# pca20054_sheet3_antenna_switches.net
KiCad netlist of a schematic drawn in Altium Designer
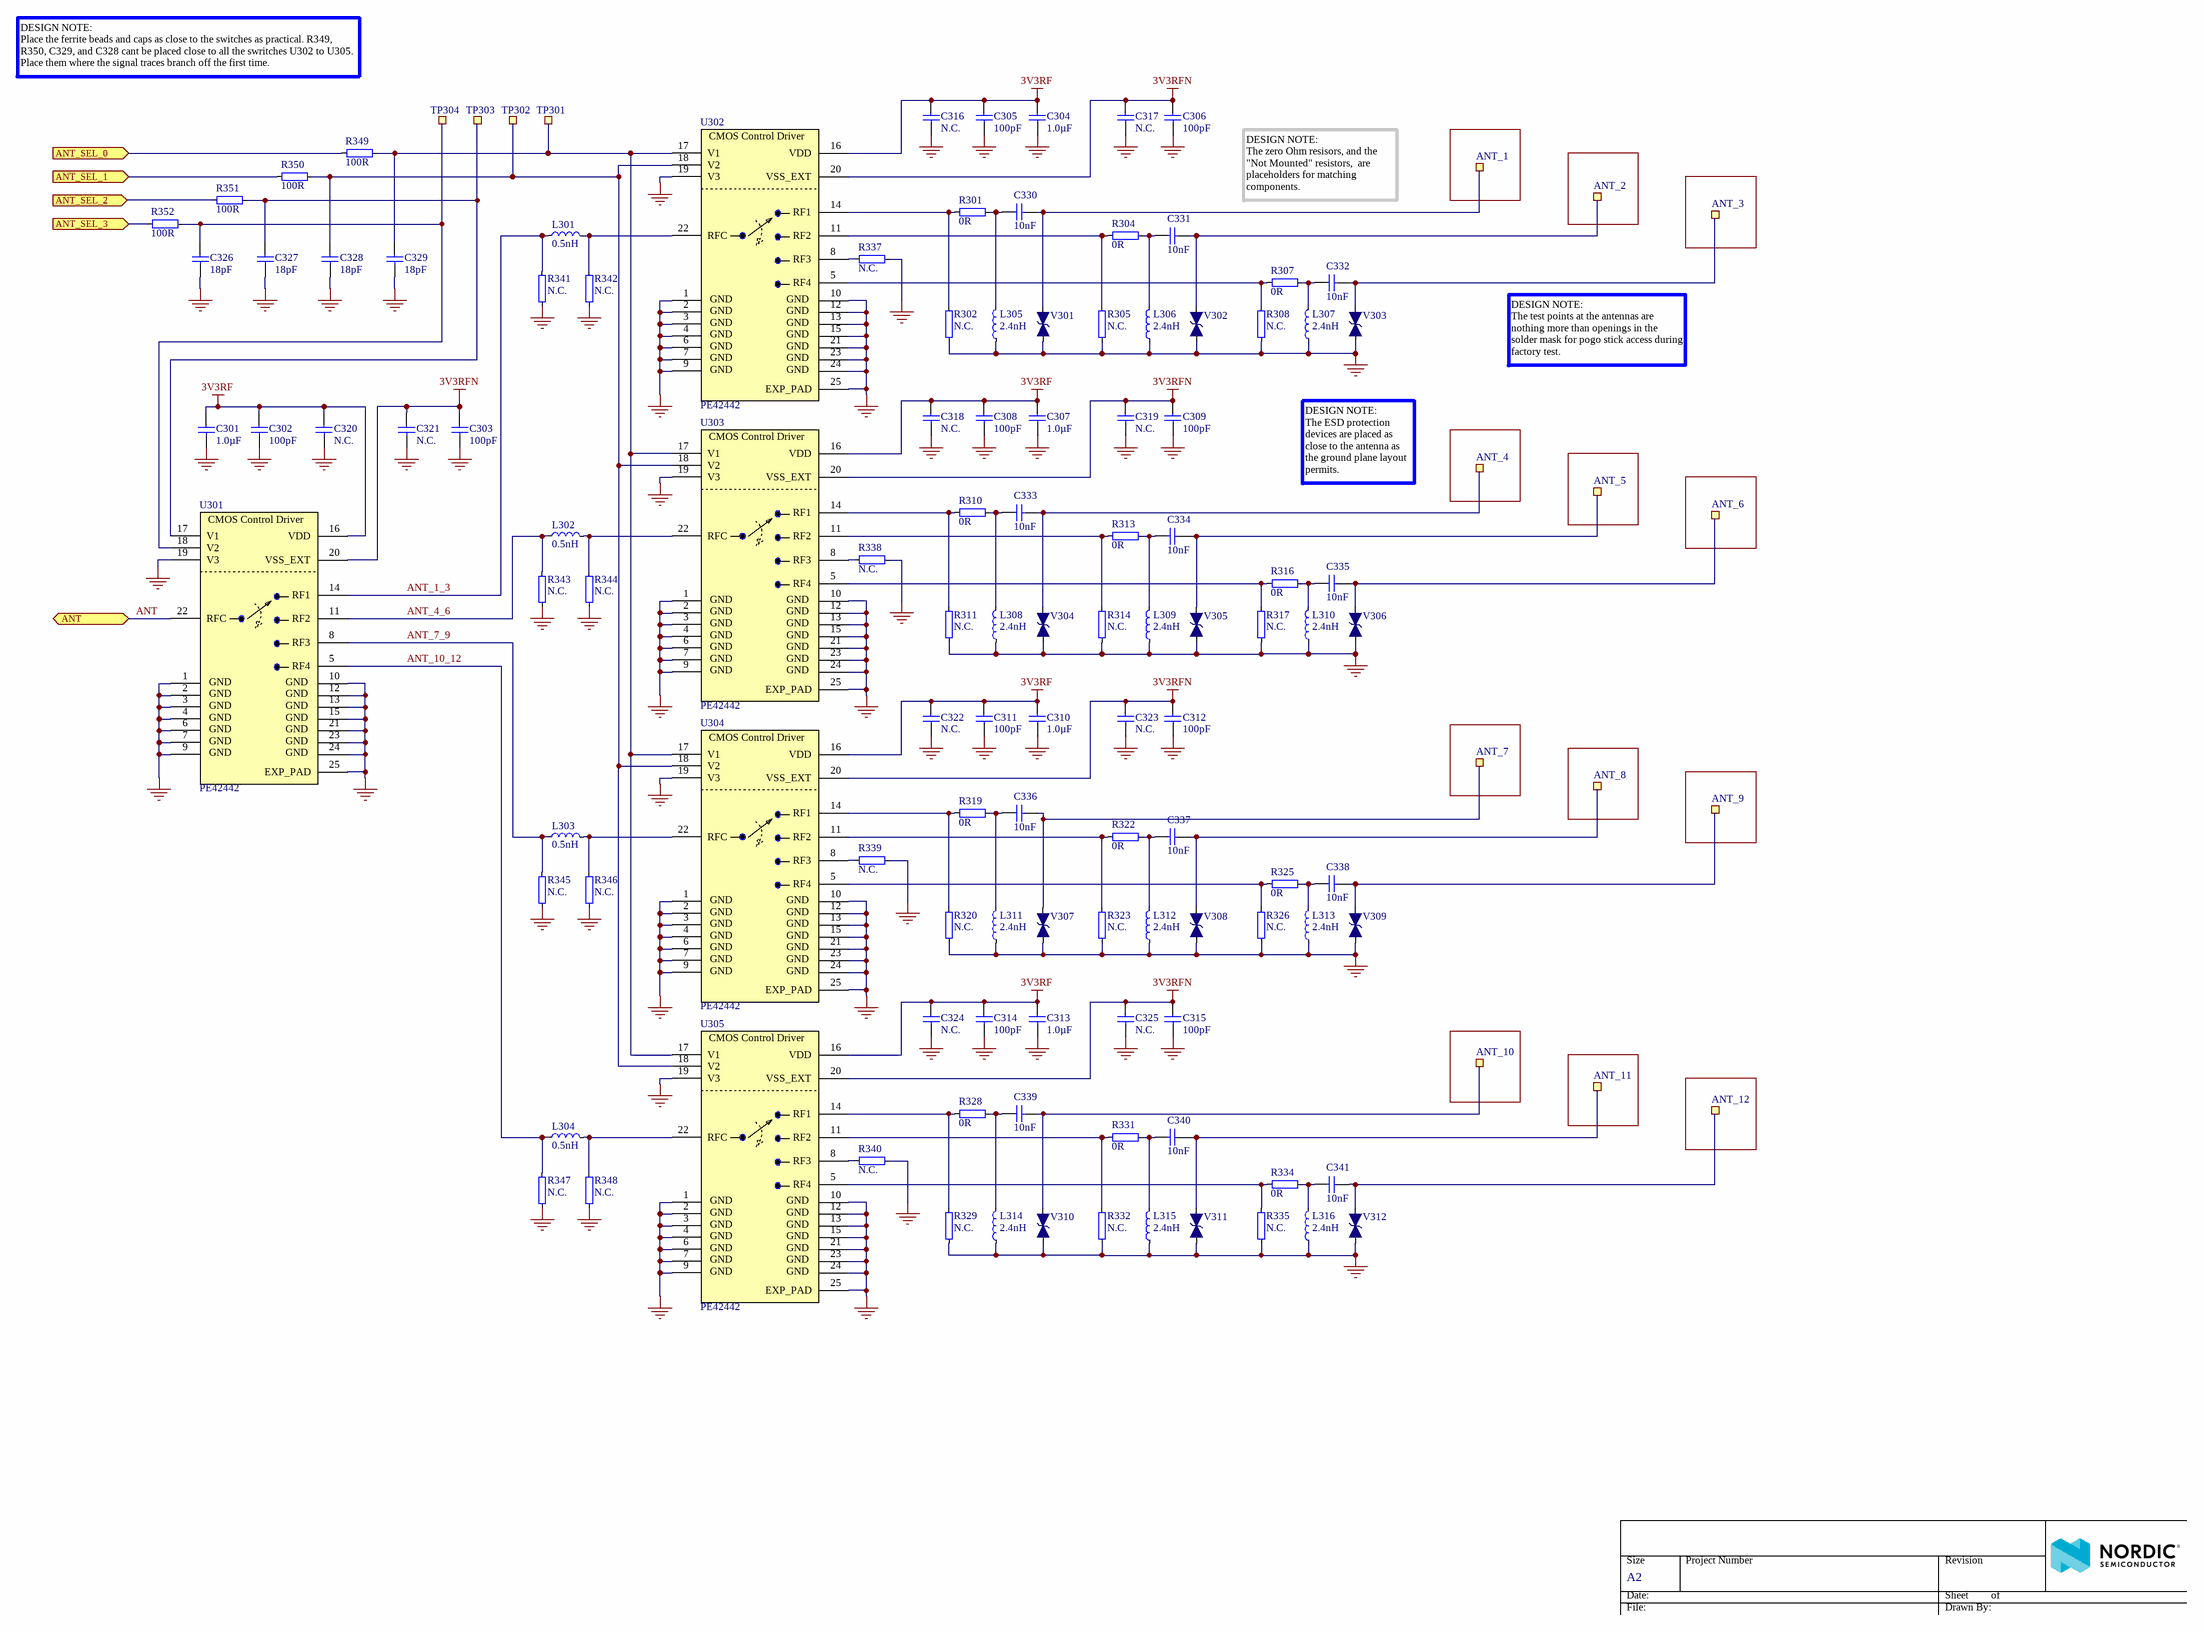
[diagram p0: pca20054_sheet3_antenna_switches.SchDoc]

(export (version "E")
  (design (tool "Eeschema 10.0.6"))
  (components
    (comp (ref "ANT_1")
      (value "Ø1.0mm,SMD")
      (footprint "TP_SMD_?.0mm")
      (description "1.0mm circular SMD testpad")
      (fields
        (field (name "PART NUMBER") "TP_SMD_Ø1.0MM")
        (field (name "MANUFACTURER") "Nordic Semiconductor")
        (field (name "PUBLISHER") "Nordic Semiconductor")
      )
      (libsource (lib "Nordic Passive DB") (part "TESTPAD"))
    )
    (comp (ref "ANT_2")
      (value "Ø1.0mm,SMD")
      (footprint "TP_SMD_?.0mm")
      (description "1.0mm circular SMD testpad")
      (fields
        (field (name "PART NUMBER") "TP_SMD_Ø1.0MM")
        (field (name "MANUFACTURER") "Nordic Semiconductor")
        (field (name "PUBLISHER") "Nordic Semiconductor")
      )
      (libsource (lib "Nordic Passive DB") (part "TESTPAD"))
    )
    (comp (ref "ANT_3")
      (value "Ø1.0mm,SMD")
      (footprint "TP_SMD_?.0mm")
      (description "1.0mm circular SMD testpad")
      (fields
        (field (name "PART NUMBER") "TP_SMD_Ø1.0MM")
        (field (name "MANUFACTURER") "Nordic Semiconductor")
        (field (name "PUBLISHER") "Nordic Semiconductor")
      )
      (libsource (lib "Nordic Passive DB") (part "TESTPAD"))
    )
    (comp (ref "ANT_4")
      (value "Ø1.0mm,SMD")
      (footprint "TP_SMD_?.0mm")
      (description "1.0mm circular SMD testpad")
      (fields
        (field (name "PART NUMBER") "TP_SMD_Ø1.0MM")
        (field (name "MANUFACTURER") "Nordic Semiconductor")
        (field (name "PUBLISHER") "Nordic Semiconductor")
      )
      (libsource (lib "Nordic Passive DB") (part "TESTPAD"))
    )
    (comp (ref "ANT_5")
      (value "Ø1.0mm,SMD")
      (footprint "TP_SMD_?.0mm")
      (description "1.0mm circular SMD testpad")
      (fields
        (field (name "PART NUMBER") "TP_SMD_Ø1.0MM")
        (field (name "MANUFACTURER") "Nordic Semiconductor")
        (field (name "PUBLISHER") "Nordic Semiconductor")
      )
      (libsource (lib "Nordic Passive DB") (part "TESTPAD"))
    )
    (comp (ref "ANT_6")
      (value "Ø1.0mm,SMD")
      (footprint "TP_SMD_?.0mm")
      (description "1.0mm circular SMD testpad")
      (fields
        (field (name "PART NUMBER") "TP_SMD_Ø1.0MM")
        (field (name "MANUFACTURER") "Nordic Semiconductor")
        (field (name "PUBLISHER") "Nordic Semiconductor")
      )
      (libsource (lib "Nordic Passive DB") (part "TESTPAD"))
    )
    (comp (ref "ANT_7")
      (value "Ø1.0mm,SMD")
      (footprint "TP_SMD_?.0mm")
      (description "1.0mm circular SMD testpad")
      (fields
        (field (name "PART NUMBER") "TP_SMD_Ø1.0MM")
        (field (name "MANUFACTURER") "Nordic Semiconductor")
        (field (name "PUBLISHER") "Nordic Semiconductor")
      )
      (libsource (lib "Nordic Passive DB") (part "TESTPAD"))
    )
    (comp (ref "ANT_8")
      (value "Ø1.0mm,SMD")
      (footprint "TP_SMD_?.0mm")
      (description "1.0mm circular SMD testpad")
      (fields
        (field (name "PART NUMBER") "TP_SMD_Ø1.0MM")
        (field (name "MANUFACTURER") "Nordic Semiconductor")
        (field (name "PUBLISHER") "Nordic Semiconductor")
      )
      (libsource (lib "Nordic Passive DB") (part "TESTPAD"))
    )
    (comp (ref "ANT_9")
      (value "Ø1.0mm,SMD")
      (footprint "TP_SMD_?.0mm")
      (description "1.0mm circular SMD testpad")
      (fields
        (field (name "PART NUMBER") "TP_SMD_Ø1.0MM")
        (field (name "MANUFACTURER") "Nordic Semiconductor")
        (field (name "PUBLISHER") "Nordic Semiconductor")
      )
      (libsource (lib "Nordic Passive DB") (part "TESTPAD"))
    )
    (comp (ref "ANT_10")
      (value "Ø1.0mm,SMD")
      (footprint "TP_SMD_?.0mm")
      (description "1.0mm circular SMD testpad")
      (fields
        (field (name "PART NUMBER") "TP_SMD_Ø1.0MM")
        (field (name "MANUFACTURER") "Nordic Semiconductor")
        (field (name "PUBLISHER") "Nordic Semiconductor")
      )
      (libsource (lib "Nordic Passive DB") (part "TESTPAD"))
    )
    (comp (ref "ANT_11")
      (value "Ø1.0mm,SMD")
      (footprint "TP_SMD_?.0mm")
      (description "1.0mm circular SMD testpad")
      (fields
        (field (name "PART NUMBER") "TP_SMD_Ø1.0MM")
        (field (name "MANUFACTURER") "Nordic Semiconductor")
        (field (name "PUBLISHER") "Nordic Semiconductor")
      )
      (libsource (lib "Nordic Passive DB") (part "TESTPAD"))
    )
    (comp (ref "ANT_12")
      (value "Ø1.0mm,SMD")
      (footprint "TP_SMD_?.0mm")
      (description "1.0mm circular SMD testpad")
      (fields
        (field (name "PART NUMBER") "TP_SMD_Ø1.0MM")
        (field (name "MANUFACTURER") "Nordic Semiconductor")
        (field (name "PUBLISHER") "Nordic Semiconductor")
      )
      (libsource (lib "Nordic Passive DB") (part "TESTPAD"))
    )
    (comp (ref "C301")
      (value "1.0µF")
      (footprint "CAPC1608X06L")
      (description "Capacitor, X7R, ±10%")
      (fields (field (name "PART NUMBER") "C0603-1µ0") (field (name "PUBLISHER") "Nordic Semiconductor"))
      (libsource (lib "Nordic Passive DB") (part "CAP"))
    )
    (comp (ref "C302")
      (value "100pF")
      (footprint "CAPC1005X04L")
      (description "Capacitor, NP0, ±5%")
      (fields (field (name "PART NUMBER") "C0402-100p") (field (name "PUBLISHER") "Nordic Semiconductor"))
      (libsource (lib "Nordic Passive DB") (part "CAP"))
    )
    (comp (ref "C303")
      (value "100pF")
      (footprint "CAPC1005X04L")
      (description "Capacitor, NP0, ±5%")
      (fields (field (name "PART NUMBER") "C0402-100p") (field (name "PUBLISHER") "Nordic Semiconductor"))
      (libsource (lib "Nordic Passive DB") (part "CAP"))
    )
    (comp (ref "C304")
      (value "1.0µF")
      (footprint "CAPC1608X06L")
      (description "Capacitor, X7R, ±10%")
      (fields (field (name "PART NUMBER") "C0603-1µ0") (field (name "PUBLISHER") "Nordic Semiconductor"))
      (libsource (lib "Nordic Passive DB") (part "CAP"))
    )
    (comp (ref "C305")
      (value "100pF")
      (footprint "CAPC1005X04L")
      (description "Capacitor, NP0, ±5%")
      (fields (field (name "PART NUMBER") "C0402-100p") (field (name "PUBLISHER") "Nordic Semiconductor"))
      (libsource (lib "Nordic Passive DB") (part "CAP"))
    )
    (comp (ref "C306")
      (value "100pF")
      (footprint "CAPC1005X04L")
      (description "Capacitor, NP0, ±5%")
      (fields (field (name "PART NUMBER") "C0402-100p") (field (name "PUBLISHER") "Nordic Semiconductor"))
      (libsource (lib "Nordic Passive DB") (part "CAP"))
    )
    (comp (ref "C307")
      (value "1.0µF")
      (footprint "CAPC1608X06L")
      (description "Capacitor, X7R, ±10%")
      (fields (field (name "PART NUMBER") "C0603-1µ0") (field (name "PUBLISHER") "Nordic Semiconductor"))
      (libsource (lib "Nordic Passive DB") (part "CAP"))
    )
    (comp (ref "C308")
      (value "100pF")
      (footprint "CAPC1005X04L")
      (description "Capacitor, NP0, ±5%")
      (fields (field (name "PART NUMBER") "C0402-100p") (field (name "PUBLISHER") "Nordic Semiconductor"))
      (libsource (lib "Nordic Passive DB") (part "CAP"))
    )
    (comp (ref "C309")
      (value "100pF")
      (footprint "CAPC1005X04L")
      (description "Capacitor, NP0, ±5%")
      (fields (field (name "PART NUMBER") "C0402-100p") (field (name "PUBLISHER") "Nordic Semiconductor"))
      (libsource (lib "Nordic Passive DB") (part "CAP"))
    )
    (comp (ref "C310")
      (value "1.0µF")
      (footprint "CAPC1608X06L")
      (description "Capacitor, X7R, ±10%")
      (fields (field (name "PART NUMBER") "C0603-1µ0") (field (name "PUBLISHER") "Nordic Semiconductor"))
      (libsource (lib "Nordic Passive DB") (part "CAP"))
    )
    (comp (ref "C311")
      (value "100pF")
      (footprint "CAPC1005X04L")
      (description "Capacitor, NP0, ±5%")
      (fields (field (name "PART NUMBER") "C0402-100p") (field (name "PUBLISHER") "Nordic Semiconductor"))
      (libsource (lib "Nordic Passive DB") (part "CAP"))
    )
    (comp (ref "C312")
      (value "100pF")
      (footprint "CAPC1005X04L")
      (description "Capacitor, NP0, ±5%")
      (fields (field (name "PART NUMBER") "C0402-100p") (field (name "PUBLISHER") "Nordic Semiconductor"))
      (libsource (lib "Nordic Passive DB") (part "CAP"))
    )
    (comp (ref "C313")
      (value "1.0µF")
      (footprint "CAPC1608X06L")
      (description "Capacitor, X7R, ±10%")
      (fields (field (name "PART NUMBER") "C0603-1µ0") (field (name "PUBLISHER") "Nordic Semiconductor"))
      (libsource (lib "Nordic Passive DB") (part "CAP"))
    )
    (comp (ref "C314")
      (value "100pF")
      (footprint "CAPC1005X04L")
      (description "Capacitor, NP0, ±5%")
      (fields (field (name "PART NUMBER") "C0402-100p") (field (name "PUBLISHER") "Nordic Semiconductor"))
      (libsource (lib "Nordic Passive DB") (part "CAP"))
    )
    (comp (ref "C315")
      (value "100pF")
      (footprint "CAPC1005X04L")
      (description "Capacitor, NP0, ±5%")
      (fields (field (name "PART NUMBER") "C0402-100p") (field (name "PUBLISHER") "Nordic Semiconductor"))
      (libsource (lib "Nordic Passive DB") (part "CAP"))
    )
    (comp (ref "C316")
      (value "N.C.")
      (footprint "CAPC1005X04L_NC")
      (description "Not mounted")
      (fields (field (name "PART NUMBER") "C0402-N.C.") (field (name "PUBLISHER") "Nordic Semiconductor"))
      (libsource (lib "Nordic Passive DB") (part "CAP"))
    )
    (comp (ref "C317")
      (value "N.C.")
      (footprint "CAPC1005X04L_NC")
      (description "Not mounted")
      (fields (field (name "PART NUMBER") "C0402-N.C.") (field (name "PUBLISHER") "Nordic Semiconductor"))
      (libsource (lib "Nordic Passive DB") (part "CAP"))
    )
    (comp (ref "C318")
      (value "N.C.")
      (footprint "CAPC1005X04L_NC")
      (description "Not mounted")
      (fields (field (name "PART NUMBER") "C0402-N.C.") (field (name "PUBLISHER") "Nordic Semiconductor"))
      (libsource (lib "Nordic Passive DB") (part "CAP"))
    )
    (comp (ref "C319")
      (value "N.C.")
      (footprint "CAPC1005X04L_NC")
      (description "Not mounted")
      (fields (field (name "PART NUMBER") "C0402-N.C.") (field (name "PUBLISHER") "Nordic Semiconductor"))
      (libsource (lib "Nordic Passive DB") (part "CAP"))
    )
    (comp (ref "C320")
      (value "N.C.")
      (footprint "CAPC1005X04L_NC")
      (description "Not mounted")
      (fields (field (name "PART NUMBER") "C0402-N.C.") (field (name "PUBLISHER") "Nordic Semiconductor"))
      (libsource (lib "Nordic Passive DB") (part "CAP"))
    )
    (comp (ref "C321")
      (value "N.C.")
      (footprint "CAPC1005X04L_NC")
      (description "Not mounted")
      (fields (field (name "PART NUMBER") "C0402-N.C.") (field (name "PUBLISHER") "Nordic Semiconductor"))
      (libsource (lib "Nordic Passive DB") (part "CAP"))
    )
    (comp (ref "C322")
      (value "N.C.")
      (footprint "CAPC1005X04L_NC")
      (description "Not mounted")
      (fields (field (name "PART NUMBER") "C0402-N.C.") (field (name "PUBLISHER") "Nordic Semiconductor"))
      (libsource (lib "Nordic Passive DB") (part "CAP"))
    )
    (comp (ref "C323")
      (value "N.C.")
      (footprint "CAPC1005X04L_NC")
      (description "Not mounted")
      (fields (field (name "PART NUMBER") "C0402-N.C.") (field (name "PUBLISHER") "Nordic Semiconductor"))
      (libsource (lib "Nordic Passive DB") (part "CAP"))
    )
    (comp (ref "C324")
      (value "N.C.")
      (footprint "CAPC1005X04L_NC")
      (description "Not mounted")
      (fields (field (name "PART NUMBER") "C0402-N.C.") (field (name "PUBLISHER") "Nordic Semiconductor"))
      (libsource (lib "Nordic Passive DB") (part "CAP"))
    )
    (comp (ref "C325")
      (value "N.C.")
      (footprint "CAPC1005X04L_NC")
      (description "Not mounted")
      (fields (field (name "PART NUMBER") "C0402-N.C.") (field (name "PUBLISHER") "Nordic Semiconductor"))
      (libsource (lib "Nordic Passive DB") (part "CAP"))
    )
    (comp (ref "C326")
      (value "18pF")
      (footprint "CAPC1005X04L")
      (description "Capacitor, NP0, ±5%")
      (fields (field (name "PART NUMBER") "C0402-18p") (field (name "PUBLISHER") "Nordic Semiconductor"))
      (libsource (lib "Nordic Passive DB") (part "CAP"))
    )
    (comp (ref "C327")
      (value "18pF")
      (footprint "CAPC1005X04L")
      (description "Capacitor, NP0, ±5%")
      (fields (field (name "PART NUMBER") "C0402-18p") (field (name "PUBLISHER") "Nordic Semiconductor"))
      (libsource (lib "Nordic Passive DB") (part "CAP"))
    )
    (comp (ref "C328")
      (value "18pF")
      (footprint "CAPC1005X04L")
      (description "Capacitor, NP0, ±5%")
      (fields (field (name "PART NUMBER") "C0402-18p") (field (name "PUBLISHER") "Nordic Semiconductor"))
      (libsource (lib "Nordic Passive DB") (part "CAP"))
    )
    (comp (ref "C329")
      (value "18pF")
      (footprint "CAPC1005X04L")
      (description "Capacitor, NP0, ±5%")
      (fields (field (name "PART NUMBER") "C0402-18p") (field (name "PUBLISHER") "Nordic Semiconductor"))
      (libsource (lib "Nordic Passive DB") (part "CAP"))
    )
    (comp (ref "C330")
      (value "10nF")
      (footprint "CAPC1005X04L")
      (description "Capacitor, X7R, ±10%")
      (fields (field (name "PART NUMBER") "C0402-10n") (field (name "PUBLISHER") "Nordic Semiconductor"))
      (libsource (lib "Nordic Passive DB") (part "CAP"))
    )
    (comp (ref "C331")
      (value "10nF")
      (footprint "CAPC1005X04L")
      (description "Capacitor, X7R, ±10%")
      (fields (field (name "PART NUMBER") "C0402-10n") (field (name "PUBLISHER") "Nordic Semiconductor"))
      (libsource (lib "Nordic Passive DB") (part "CAP"))
    )
    (comp (ref "C332")
      (value "10nF")
      (footprint "CAPC1005X04L")
      (description "Capacitor, X7R, ±10%")
      (fields (field (name "PART NUMBER") "C0402-10n") (field (name "PUBLISHER") "Nordic Semiconductor"))
      (libsource (lib "Nordic Passive DB") (part "CAP"))
    )
    (comp (ref "C333")
      (value "10nF")
      (footprint "CAPC1005X04L")
      (description "Capacitor, X7R, ±10%")
      (fields (field (name "PART NUMBER") "C0402-10n") (field (name "PUBLISHER") "Nordic Semiconductor"))
      (libsource (lib "Nordic Passive DB") (part "CAP"))
    )
    (comp (ref "C334")
      (value "10nF")
      (footprint "CAPC1005X04L")
      (description "Capacitor, X7R, ±10%")
      (fields (field (name "PART NUMBER") "C0402-10n") (field (name "PUBLISHER") "Nordic Semiconductor"))
      (libsource (lib "Nordic Passive DB") (part "CAP"))
    )
    (comp (ref "C335")
      (value "10nF")
      (footprint "CAPC1005X04L")
      (description "Capacitor, X7R, ±10%")
      (fields (field (name "PART NUMBER") "C0402-10n") (field (name "PUBLISHER") "Nordic Semiconductor"))
      (libsource (lib "Nordic Passive DB") (part "CAP"))
    )
    (comp (ref "C336")
      (value "10nF")
      (footprint "CAPC1005X04L")
      (description "Capacitor, X7R, ±10%")
      (fields (field (name "PART NUMBER") "C0402-10n") (field (name "PUBLISHER") "Nordic Semiconductor"))
      (libsource (lib "Nordic Passive DB") (part "CAP"))
    )
    (comp (ref "C337")
      (value "10nF")
      (footprint "CAPC1005X04L")
      (description "Capacitor, X7R, ±10%")
      (fields (field (name "PART NUMBER") "C0402-10n") (field (name "PUBLISHER") "Nordic Semiconductor"))
      (libsource (lib "Nordic Passive DB") (part "CAP"))
    )
    (comp (ref "C338")
      (value "10nF")
      (footprint "CAPC1005X04L")
      (description "Capacitor, X7R, ±10%")
      (fields (field (name "PART NUMBER") "C0402-10n") (field (name "PUBLISHER") "Nordic Semiconductor"))
      (libsource (lib "Nordic Passive DB") (part "CAP"))
    )
    (comp (ref "C339")
      (value "10nF")
      (footprint "CAPC1005X04L")
      (description "Capacitor, X7R, ±10%")
      (fields (field (name "PART NUMBER") "C0402-10n") (field (name "PUBLISHER") "Nordic Semiconductor"))
      (libsource (lib "Nordic Passive DB") (part "CAP"))
    )
    (comp (ref "C340")
      (value "10nF")
      (footprint "CAPC1005X04L")
      (description "Capacitor, X7R, ±10%")
      (fields (field (name "PART NUMBER") "C0402-10n") (field (name "PUBLISHER") "Nordic Semiconductor"))
      (libsource (lib "Nordic Passive DB") (part "CAP"))
    )
    (comp (ref "C341")
      (value "10nF")
      (footprint "CAPC1005X04L")
      (description "Capacitor, X7R, ±10%")
      (fields (field (name "PART NUMBER") "C0402-10n") (field (name "PUBLISHER") "Nordic Semiconductor"))
      (libsource (lib "Nordic Passive DB") (part "CAP"))
    )
    (comp (ref "L301")
      (value "0.5nH")
      (footprint "INDC1005X04L")
      (description "Inductor, 1A, ±0.1nH")
      (fields
        (field (name "PART NUMBER") "L0402-0n5")
        (field (name "MANUFACTURER") "TDK Corporation")
        (field (name "PUBLISHER") "Nordic Semiconductor")
      )
      (libsource (lib "Nordic Passive DB") (part "IND"))
    )
    (comp (ref "L302")
      (value "0.5nH")
      (footprint "INDC1005X04L")
      (description "Inductor, 1A, ±0.1nH")
      (fields
        (field (name "PART NUMBER") "L0402-0n5")
        (field (name "MANUFACTURER") "TDK Corporation")
        (field (name "PUBLISHER") "Nordic Semiconductor")
      )
      (libsource (lib "Nordic Passive DB") (part "IND"))
    )
    (comp (ref "L303")
      (value "0.5nH")
      (footprint "INDC1005X04L")
      (description "Inductor, 1A, ±0.1nH")
      (fields
        (field (name "PART NUMBER") "L0402-0n5")
        (field (name "MANUFACTURER") "TDK Corporation")
        (field (name "PUBLISHER") "Nordic Semiconductor")
      )
      (libsource (lib "Nordic Passive DB") (part "IND"))
    )
    (comp (ref "L304")
      (value "0.5nH")
      (footprint "INDC1005X04L")
      (description "Inductor, 1A, ±0.1nH")
      (fields
        (field (name "PART NUMBER") "L0402-0n5")
        (field (name "MANUFACTURER") "TDK Corporation")
        (field (name "PUBLISHER") "Nordic Semiconductor")
      )
      (libsource (lib "Nordic Passive DB") (part "IND"))
    )
    (comp (ref "L305")
      (value "2.4nH")
      (footprint "INDC1005X04L")
      (description "Inductor, 220mA, ±0.1nH")
      (fields (field (name "PART NUMBER") "L0402-2n4") (field (name "PUBLISHER") "Nordic Semiconductor"))
      (libsource (lib "Nordic Passive DB") (part "IND"))
    )
    (comp (ref "L306")
      (value "2.4nH")
      (footprint "INDC1005X04L")
      (description "Inductor, 220mA, ±0.1nH")
      (fields (field (name "PART NUMBER") "L0402-2n4") (field (name "PUBLISHER") "Nordic Semiconductor"))
      (libsource (lib "Nordic Passive DB") (part "IND"))
    )
    (comp (ref "L307")
      (value "2.4nH")
      (footprint "INDC1005X04L")
      (description "Inductor, 220mA, ±0.1nH")
      (fields (field (name "PART NUMBER") "L0402-2n4") (field (name "PUBLISHER") "Nordic Semiconductor"))
      (libsource (lib "Nordic Passive DB") (part "IND"))
    )
    (comp (ref "L308")
      (value "2.4nH")
      (footprint "INDC1005X04L")
      (description "Inductor, 220mA, ±0.1nH")
      (fields (field (name "PART NUMBER") "L0402-2n4") (field (name "PUBLISHER") "Nordic Semiconductor"))
      (libsource (lib "Nordic Passive DB") (part "IND"))
    )
    (comp (ref "L309")
      (value "2.4nH")
      (footprint "INDC1005X04L")
      (description "Inductor, 220mA, ±0.1nH")
      (fields (field (name "PART NUMBER") "L0402-2n4") (field (name "PUBLISHER") "Nordic Semiconductor"))
      (libsource (lib "Nordic Passive DB") (part "IND"))
    )
    (comp (ref "L310")
      (value "2.4nH")
      (footprint "INDC1005X04L")
      (description "Inductor, 220mA, ±0.1nH")
      (fields (field (name "PART NUMBER") "L0402-2n4") (field (name "PUBLISHER") "Nordic Semiconductor"))
      (libsource (lib "Nordic Passive DB") (part "IND"))
    )
    (comp (ref "L311")
      (value "2.4nH")
      (footprint "INDC1005X04L")
      (description "Inductor, 220mA, ±0.1nH")
      (fields (field (name "PART NUMBER") "L0402-2n4") (field (name "PUBLISHER") "Nordic Semiconductor"))
      (libsource (lib "Nordic Passive DB") (part "IND"))
    )
    (comp (ref "L312")
      (value "2.4nH")
      (footprint "INDC1005X04L")
      (description "Inductor, 220mA, ±0.1nH")
      (fields (field (name "PART NUMBER") "L0402-2n4") (field (name "PUBLISHER") "Nordic Semiconductor"))
      (libsource (lib "Nordic Passive DB") (part "IND"))
    )
    (comp (ref "L313")
      (value "2.4nH")
      (footprint "INDC1005X04L")
      (description "Inductor, 220mA, ±0.1nH")
      (fields (field (name "PART NUMBER") "L0402-2n4") (field (name "PUBLISHER") "Nordic Semiconductor"))
      (libsource (lib "Nordic Passive DB") (part "IND"))
    )
    (comp (ref "L314")
      (value "2.4nH")
      (footprint "INDC1005X04L")
      (description "Inductor, 220mA, ±0.1nH")
      (fields (field (name "PART NUMBER") "L0402-2n4") (field (name "PUBLISHER") "Nordic Semiconductor"))
      (libsource (lib "Nordic Passive DB") (part "IND"))
    )
    (comp (ref "L315")
      (value "2.4nH")
      (footprint "INDC1005X04L")
      (description "Inductor, 220mA, ±0.1nH")
      (fields (field (name "PART NUMBER") "L0402-2n4") (field (name "PUBLISHER") "Nordic Semiconductor"))
      (libsource (lib "Nordic Passive DB") (part "IND"))
    )
    (comp (ref "L316")
      (value "2.4nH")
      (footprint "INDC1005X04L")
      (description "Inductor, 220mA, ±0.1nH")
      (fields (field (name "PART NUMBER") "L0402-2n4") (field (name "PUBLISHER") "Nordic Semiconductor"))
      (libsource (lib "Nordic Passive DB") (part "IND"))
    )
    (comp (ref "R301")
      (value "0R")
      (footprint "RESC1005X04L")
      (description "Resistor, ±5%, 0.063W")
      (fields (field (name "PART NUMBER") "R0402-0R") (field (name "PUBLISHER") "Nordic Semiconductor"))
      (libsource (lib "Nordic Passive DB") (part "RES"))
    )
    (comp (ref "R302")
      (value "N.C.")
      (footprint "RESC1005X04L_NC")
      (description "Not mounted")
      (fields (field (name "PART NUMBER") "R0402-N.C.") (field (name "PUBLISHER") "Nordic Semiconductor"))
      (libsource (lib "Nordic Passive DB") (part "RES"))
    )
    (comp (ref "R304")
      (value "0R")
      (footprint "RESC1005X04L")
      (description "Resistor, ±5%, 0.063W")
      (fields (field (name "PART NUMBER") "R0402-0R") (field (name "PUBLISHER") "Nordic Semiconductor"))
      (libsource (lib "Nordic Passive DB") (part "RES"))
    )
    (comp (ref "R305")
      (value "N.C.")
      (footprint "RESC1005X04L_NC")
      (description "Not mounted")
      (fields (field (name "PART NUMBER") "R0402-N.C.") (field (name "PUBLISHER") "Nordic Semiconductor"))
      (libsource (lib "Nordic Passive DB") (part "RES"))
    )
    (comp (ref "R307")
      (value "0R")
      (footprint "RESC1005X04L")
      (description "Resistor, ±5%, 0.063W")
      (fields (field (name "PART NUMBER") "R0402-0R") (field (name "PUBLISHER") "Nordic Semiconductor"))
      (libsource (lib "Nordic Passive DB") (part "RES"))
    )
    (comp (ref "R308")
      (value "N.C.")
      (footprint "RESC1005X04L_NC")
      (description "Not mounted")
      (fields (field (name "PART NUMBER") "R0402-N.C.") (field (name "PUBLISHER") "Nordic Semiconductor"))
      (libsource (lib "Nordic Passive DB") (part "RES"))
    )
    (comp (ref "R310")
      (value "0R")
      (footprint "RESC1005X04L")
      (description "Resistor, ±5%, 0.063W")
      (fields (field (name "PART NUMBER") "R0402-0R") (field (name "PUBLISHER") "Nordic Semiconductor"))
      (libsource (lib "Nordic Passive DB") (part "RES"))
    )
    (comp (ref "R311")
      (value "N.C.")
      (footprint "RESC1005X04L_NC")
      (description "Not mounted")
      (fields (field (name "PART NUMBER") "R0402-N.C.") (field (name "PUBLISHER") "Nordic Semiconductor"))
      (libsource (lib "Nordic Passive DB") (part "RES"))
    )
    (comp (ref "R313")
      (value "0R")
      (footprint "RESC1005X04L")
      (description "Resistor, ±5%, 0.063W")
      (fields (field (name "PART NUMBER") "R0402-0R") (field (name "PUBLISHER") "Nordic Semiconductor"))
      (libsource (lib "Nordic Passive DB") (part "RES"))
    )
    (comp (ref "R314")
      (value "N.C.")
      (footprint "RESC1005X04L_NC")
      (description "Not mounted")
      (fields (field (name "PART NUMBER") "R0402-N.C.") (field (name "PUBLISHER") "Nordic Semiconductor"))
      (libsource (lib "Nordic Passive DB") (part "RES"))
    )
    (comp (ref "R316")
      (value "0R")
      (footprint "RESC1005X04L")
      (description "Resistor, ±5%, 0.063W")
      (fields (field (name "PART NUMBER") "R0402-0R") (field (name "PUBLISHER") "Nordic Semiconductor"))
      (libsource (lib "Nordic Passive DB") (part "RES"))
    )
    (comp (ref "R317")
      (value "N.C.")
      (footprint "RESC1005X04L_NC")
      (description "Not mounted")
      (fields (field (name "PART NUMBER") "R0402-N.C.") (field (name "PUBLISHER") "Nordic Semiconductor"))
      (libsource (lib "Nordic Passive DB") (part "RES"))
    )
    (comp (ref "R319")
      (value "0R")
      (footprint "RESC1005X04L")
      (description "Resistor, ±5%, 0.063W")
      (fields (field (name "PART NUMBER") "R0402-0R") (field (name "PUBLISHER") "Nordic Semiconductor"))
      (libsource (lib "Nordic Passive DB") (part "RES"))
    )
    (comp (ref "R320")
      (value "N.C.")
      (footprint "RESC1005X04L_NC")
      (description "Not mounted")
      (fields (field (name "PART NUMBER") "R0402-N.C.") (field (name "PUBLISHER") "Nordic Semiconductor"))
      (libsource (lib "Nordic Passive DB") (part "RES"))
    )
    (comp (ref "R322")
      (value "0R")
      (footprint "RESC1005X04L")
      (description "Resistor, ±5%, 0.063W")
      (fields (field (name "PART NUMBER") "R0402-0R") (field (name "PUBLISHER") "Nordic Semiconductor"))
      (libsource (lib "Nordic Passive DB") (part "RES"))
    )
    (comp (ref "R323")
      (value "N.C.")
      (footprint "RESC1005X04L_NC")
      (description "Not mounted")
      (fields (field (name "PART NUMBER") "R0402-N.C.") (field (name "PUBLISHER") "Nordic Semiconductor"))
      (libsource (lib "Nordic Passive DB") (part "RES"))
    )
    (comp (ref "R325")
      (value "0R")
      (footprint "RESC1005X04L")
      (description "Resistor, ±5%, 0.063W")
      (fields (field (name "PART NUMBER") "R0402-0R") (field (name "PUBLISHER") "Nordic Semiconductor"))
      (libsource (lib "Nordic Passive DB") (part "RES"))
    )
    (comp (ref "R326")
      (value "N.C.")
      (footprint "RESC1005X04L_NC")
      (description "Not mounted")
      (fields (field (name "PART NUMBER") "R0402-N.C.") (field (name "PUBLISHER") "Nordic Semiconductor"))
      (libsource (lib "Nordic Passive DB") (part "RES"))
    )
    (comp (ref "R328")
      (value "0R")
      (footprint "RESC1005X04L")
      (description "Resistor, ±5%, 0.063W")
      (fields (field (name "PART NUMBER") "R0402-0R") (field (name "PUBLISHER") "Nordic Semiconductor"))
      (libsource (lib "Nordic Passive DB") (part "RES"))
    )
    (comp (ref "R329")
      (value "N.C.")
      (footprint "RESC1005X04L_NC")
      (description "Not mounted")
      (fields (field (name "PART NUMBER") "R0402-N.C.") (field (name "PUBLISHER") "Nordic Semiconductor"))
      (libsource (lib "Nordic Passive DB") (part "RES"))
    )
    (comp (ref "R331")
      (value "0R")
      (footprint "RESC1005X04L")
      (description "Resistor, ±5%, 0.063W")
      (fields (field (name "PART NUMBER") "R0402-0R") (field (name "PUBLISHER") "Nordic Semiconductor"))
      (libsource (lib "Nordic Passive DB") (part "RES"))
    )
    (comp (ref "R332")
      (value "N.C.")
      (footprint "RESC1005X04L_NC")
      (description "Not mounted")
      (fields (field (name "PART NUMBER") "R0402-N.C.") (field (name "PUBLISHER") "Nordic Semiconductor"))
      (libsource (lib "Nordic Passive DB") (part "RES"))
    )
    (comp (ref "R334")
      (value "0R")
      (footprint "RESC1005X04L")
      (description "Resistor, ±5%, 0.063W")
      (fields (field (name "PART NUMBER") "R0402-0R") (field (name "PUBLISHER") "Nordic Semiconductor"))
      (libsource (lib "Nordic Passive DB") (part "RES"))
    )
    (comp (ref "R335")
      (value "N.C.")
      (footprint "RESC1005X04L_NC")
      (description "Not mounted")
      (fields (field (name "PART NUMBER") "R0402-N.C.") (field (name "PUBLISHER") "Nordic Semiconductor"))
      (libsource (lib "Nordic Passive DB") (part "RES"))
    )
    (comp (ref "R337")
      (value "N.C.")
      (footprint "RESC1005X04L_NC")
      (description "Not mounted")
      (fields (field (name "PART NUMBER") "R0402-N.C.") (field (name "PUBLISHER") "Nordic Semiconductor"))
      (libsource (lib "Nordic Passive DB") (part "RES"))
    )
    (comp (ref "R338")
      (value "N.C.")
      (footprint "RESC1005X04L_NC")
      (description "Not mounted")
      (fields (field (name "PART NUMBER") "R0402-N.C.") (field (name "PUBLISHER") "Nordic Semiconductor"))
      (libsource (lib "Nordic Passive DB") (part "RES"))
    )
    (comp (ref "R339")
      (value "N.C.")
      (footprint "RESC1005X04L_NC")
      (description "Not mounted")
      (fields (field (name "PART NUMBER") "R0402-N.C.") (field (name "PUBLISHER") "Nordic Semiconductor"))
      (libsource (lib "Nordic Passive DB") (part "RES"))
    )
    (comp (ref "R340")
      (value "N.C.")
      (footprint "RESC1005X04L_NC")
      (description "Not mounted")
      (fields (field (name "PART NUMBER") "R0402-N.C.") (field (name "PUBLISHER") "Nordic Semiconductor"))
      (libsource (lib "Nordic Passive DB") (part "RES"))
    )
    (comp (ref "R341")
      (value "N.C.")
      (footprint "RESC1005X04L_NC")
      (description "Not mounted")
      (fields (field (name "PART NUMBER") "R0402-N.C.") (field (name "PUBLISHER") "Nordic Semiconductor"))
      (libsource (lib "Nordic Passive DB") (part "RES"))
    )
    (comp (ref "R342")
      (value "N.C.")
      (footprint "RESC1005X04L_NC")
      (description "Not mounted")
      (fields (field (name "PART NUMBER") "R0402-N.C.") (field (name "PUBLISHER") "Nordic Semiconductor"))
      (libsource (lib "Nordic Passive DB") (part "RES"))
    )
    (comp (ref "R343")
      (value "N.C.")
      (footprint "RESC1005X04L_NC")
      (description "Not mounted")
      (fields (field (name "PART NUMBER") "R0402-N.C.") (field (name "PUBLISHER") "Nordic Semiconductor"))
      (libsource (lib "Nordic Passive DB") (part "RES"))
    )
    (comp (ref "R344")
      (value "N.C.")
      (footprint "RESC1005X04L_NC")
      (description "Not mounted")
      (fields (field (name "PART NUMBER") "R0402-N.C.") (field (name "PUBLISHER") "Nordic Semiconductor"))
      (libsource (lib "Nordic Passive DB") (part "RES"))
    )
    (comp (ref "R345")
      (value "N.C.")
      (footprint "RESC1005X04L_NC")
      (description "Not mounted")
      (fields (field (name "PART NUMBER") "R0402-N.C.") (field (name "PUBLISHER") "Nordic Semiconductor"))
      (libsource (lib "Nordic Passive DB") (part "RES"))
    )
    (comp (ref "R346")
      (value "N.C.")
      (footprint "RESC1005X04L_NC")
      (description "Not mounted")
      (fields (field (name "PART NUMBER") "R0402-N.C.") (field (name "PUBLISHER") "Nordic Semiconductor"))
      (libsource (lib "Nordic Passive DB") (part "RES"))
    )
    (comp (ref "R347")
      (value "N.C.")
      (footprint "RESC1005X04L_NC")
      (description "Not mounted")
      (fields (field (name "PART NUMBER") "R0402-N.C.") (field (name "PUBLISHER") "Nordic Semiconductor"))
      (libsource (lib "Nordic Passive DB") (part "RES"))
    )
    (comp (ref "R348")
      (value "N.C.")
      (footprint "RESC1005X04L_NC")
      (description "Not mounted")
      (fields (field (name "PART NUMBER") "R0402-N.C.") (field (name "PUBLISHER") "Nordic Semiconductor"))
      (libsource (lib "Nordic Passive DB") (part "RES"))
    )
    (comp (ref "R349")
      (value "100R")
      (footprint "RESC1005X04L")
      (description "Resistor, ±1%, 0.063W")
      (fields (field (name "PART NUMBER") "R0402-100") (field (name "PUBLISHER") "Nordic Semiconductor"))
      (libsource (lib "Nordic Passive DB") (part "RES"))
    )
    (comp (ref "R350")
      (value "100R")
      (footprint "RESC1005X04L")
      (description "Resistor, ±1%, 0.063W")
      (fields (field (name "PART NUMBER") "R0402-100") (field (name "PUBLISHER") "Nordic Semiconductor"))
      (libsource (lib "Nordic Passive DB") (part "RES"))
    )
    (comp (ref "R351")
      (value "100R")
      (footprint "RESC1005X04L")
      (description "Resistor, ±1%, 0.063W")
      (fields (field (name "PART NUMBER") "R0402-100") (field (name "PUBLISHER") "Nordic Semiconductor"))
      (libsource (lib "Nordic Passive DB") (part "RES"))
    )
    (comp (ref "R352")
      (value "100R")
      (footprint "RESC1005X04L")
      (description "Resistor, ±1%, 0.063W")
      (fields (field (name "PART NUMBER") "R0402-100") (field (name "PUBLISHER") "Nordic Semiconductor"))
      (libsource (lib "Nordic Passive DB") (part "RES"))
    )
    (comp (ref "TP301")
      (value "Ø1.0mm,SMD")
      (footprint "TP_SMD_?.0mm")
      (description "1.0mm circular SMD testpad")
      (fields
        (field (name "PART NUMBER") "TP_SMD_Ø1.0MM")
        (field (name "MANUFACTURER") "Nordic Semiconductor")
        (field (name "PUBLISHER") "Nordic Semiconductor")
      )
      (libsource (lib "Nordic Passive DB") (part "TESTPAD"))
    )
    (comp (ref "TP302")
      (value "Ø1.0mm,SMD")
      (footprint "TP_SMD_?.0mm")
      (description "1.0mm circular SMD testpad")
      (fields
        (field (name "PART NUMBER") "TP_SMD_Ø1.0MM")
        (field (name "MANUFACTURER") "Nordic Semiconductor")
        (field (name "PUBLISHER") "Nordic Semiconductor")
      )
      (libsource (lib "Nordic Passive DB") (part "TESTPAD"))
    )
    (comp (ref "TP303")
      (value "Ø1.0mm,SMD")
      (footprint "TP_SMD_?.0mm")
      (description "1.0mm circular SMD testpad")
      (fields
        (field (name "PART NUMBER") "TP_SMD_Ø1.0MM")
        (field (name "MANUFACTURER") "Nordic Semiconductor")
        (field (name "PUBLISHER") "Nordic Semiconductor")
      )
      (libsource (lib "Nordic Passive DB") (part "TESTPAD"))
    )
    (comp (ref "TP304")
      (value "Ø1.0mm,SMD")
      (footprint "TP_SMD_?.0mm")
      (description "1.0mm circular SMD testpad")
      (fields
        (field (name "PART NUMBER") "TP_SMD_Ø1.0MM")
        (field (name "MANUFACTURER") "Nordic Semiconductor")
        (field (name "PUBLISHER") "Nordic Semiconductor")
      )
      (libsource (lib "Nordic Passive DB") (part "TESTPAD"))
    )
    (comp (ref "U301")
      (value "PE42442")
      (footprint "QFN50P400X400X80_HS-25N")
      (description "UltraCMOS SP4T RF Switch 30 MHz-6 GHz")
      (fields
        (field (name "MANUFACTURER") "Peregrine Semiconductors")
        (field (name "PUBLISHER") "Nordic Semiconductor")
      )
      (libsource (lib "Nordic Active DB") (part "PE42442"))
    )
    (comp (ref "U302")
      (value "PE42442")
      (footprint "QFN50P400X400X80_HS-25N")
      (description "UltraCMOS SP4T RF Switch 30 MHz-6 GHz")
      (fields
        (field (name "MANUFACTURER") "Peregrine Semiconductors")
        (field (name "PUBLISHER") "Nordic Semiconductor")
      )
      (libsource (lib "Nordic Active DB") (part "PE42442"))
    )
    (comp (ref "U303")
      (value "PE42442")
      (footprint "QFN50P400X400X80_HS-25N")
      (description "UltraCMOS SP4T RF Switch 30 MHz-6 GHz")
      (fields
        (field (name "MANUFACTURER") "Peregrine Semiconductors")
        (field (name "PUBLISHER") "Nordic Semiconductor")
      )
      (libsource (lib "Nordic Active DB") (part "PE42442"))
    )
    (comp (ref "U304")
      (value "PE42442")
      (footprint "QFN50P400X400X80_HS-25N")
      (description "UltraCMOS SP4T RF Switch 30 MHz-6 GHz")
      (fields
        (field (name "MANUFACTURER") "Peregrine Semiconductors")
        (field (name "PUBLISHER") "Nordic Semiconductor")
      )
      (libsource (lib "Nordic Active DB") (part "PE42442"))
    )
    (comp (ref "U305")
      (value "PE42442")
      (footprint "QFN50P400X400X80_HS-25N")
      (description "UltraCMOS SP4T RF Switch 30 MHz-6 GHz")
      (fields
        (field (name "MANUFACTURER") "Peregrine Semiconductors")
        (field (name "PUBLISHER") "Nordic Semiconductor")
      )
      (libsource (lib "Nordic Active DB") (part "PE42442"))
    )
    (comp (ref "V301")
      (value "LXES15AAA1-133")
      (footprint "RESC1005X04L")
      (description "TVS DIODE 15VWM 0402")
      (fields (field (name "MANUFACTURER") "Murata") (field (name "PUBLISHER") "Nordic Semiconductor"))
      (libsource (lib "Nordic Discrete DB") (part "D{colon}SUPP"))
    )
    (comp (ref "V302")
      (value "LXES15AAA1-133")
      (footprint "RESC1005X04L")
      (description "TVS DIODE 15VWM 0402")
      (fields (field (name "MANUFACTURER") "Murata") (field (name "PUBLISHER") "Nordic Semiconductor"))
      (libsource (lib "Nordic Discrete DB") (part "D{colon}SUPP"))
    )
    (comp (ref "V303")
      (value "LXES15AAA1-133")
      (footprint "RESC1005X04L")
      (description "TVS DIODE 15VWM 0402")
      (fields (field (name "MANUFACTURER") "Murata") (field (name "PUBLISHER") "Nordic Semiconductor"))
      (libsource (lib "Nordic Discrete DB") (part "D{colon}SUPP"))
    )
    (comp (ref "V304")
      (value "LXES15AAA1-133")
      (footprint "RESC1005X04L")
      (description "TVS DIODE 15VWM 0402")
      (fields (field (name "MANUFACTURER") "Murata") (field (name "PUBLISHER") "Nordic Semiconductor"))
      (libsource (lib "Nordic Discrete DB") (part "D{colon}SUPP"))
    )
    (comp (ref "V305")
      (value "LXES15AAA1-133")
      (footprint "RESC1005X04L")
      (description "TVS DIODE 15VWM 0402")
      (fields (field (name "MANUFACTURER") "Murata") (field (name "PUBLISHER") "Nordic Semiconductor"))
      (libsource (lib "Nordic Discrete DB") (part "D{colon}SUPP"))
    )
    (comp (ref "V306")
      (value "LXES15AAA1-133")
      (footprint "RESC1005X04L")
      (description "TVS DIODE 15VWM 0402")
      (fields (field (name "MANUFACTURER") "Murata") (field (name "PUBLISHER") "Nordic Semiconductor"))
      (libsource (lib "Nordic Discrete DB") (part "D{colon}SUPP"))
    )
    (comp (ref "V307")
      (value "LXES15AAA1-133")
      (footprint "RESC1005X04L")
      (description "TVS DIODE 15VWM 0402")
      (fields (field (name "MANUFACTURER") "Murata") (field (name "PUBLISHER") "Nordic Semiconductor"))
      (libsource (lib "Nordic Discrete DB") (part "D{colon}SUPP"))
    )
    (comp (ref "V308")
      (value "LXES15AAA1-133")
      (footprint "RESC1005X04L")
      (description "TVS DIODE 15VWM 0402")
      (fields (field (name "MANUFACTURER") "Murata") (field (name "PUBLISHER") "Nordic Semiconductor"))
      (libsource (lib "Nordic Discrete DB") (part "D{colon}SUPP"))
    )
    (comp (ref "V309")
      (value "LXES15AAA1-133")
      (footprint "RESC1005X04L")
      (description "TVS DIODE 15VWM 0402")
      (fields (field (name "MANUFACTURER") "Murata") (field (name "PUBLISHER") "Nordic Semiconductor"))
      (libsource (lib "Nordic Discrete DB") (part "D{colon}SUPP"))
    )
    (comp (ref "V310")
      (value "LXES15AAA1-133")
      (footprint "RESC1005X04L")
      (description "TVS DIODE 15VWM 0402")
      (fields (field (name "MANUFACTURER") "Murata") (field (name "PUBLISHER") "Nordic Semiconductor"))
      (libsource (lib "Nordic Discrete DB") (part "D{colon}SUPP"))
    )
    (comp (ref "V311")
      (value "LXES15AAA1-133")
      (footprint "RESC1005X04L")
      (description "TVS DIODE 15VWM 0402")
      (fields (field (name "MANUFACTURER") "Murata") (field (name "PUBLISHER") "Nordic Semiconductor"))
      (libsource (lib "Nordic Discrete DB") (part "D{colon}SUPP"))
    )
    (comp (ref "V312")
      (value "LXES15AAA1-133")
      (footprint "RESC1005X04L")
      (description "TVS DIODE 15VWM 0402")
      (fields (field (name "MANUFACTURER") "Murata") (field (name "PUBLISHER") "Nordic Semiconductor"))
      (libsource (lib "Nordic Discrete DB") (part "D{colon}SUPP"))
    )
  )
  (nets
    (net (code "1") (name "/ANT") (class "Default")
      (node (ref "U301") (pin "22") (pinfunction "RFC_22") (pintype "passive"))
    )
    (net (code "2") (name "/ANT_1_3") (class "Default")
      (node (ref "L301") (pin "1") (pinfunction "1_1") (pintype "passive"))
      (node (ref "R341") (pin "2") (pinfunction "2_2") (pintype "passive"))
      (node (ref "U301") (pin "14") (pinfunction "RF1_14") (pintype "passive"))
    )
    (net (code "3") (name "/ANT_4_6") (class "Default")
      (node (ref "L302") (pin "1") (pinfunction "1_1") (pintype "passive"))
      (node (ref "R343") (pin "2") (pinfunction "2_2") (pintype "passive"))
      (node (ref "U301") (pin "11") (pinfunction "RF2_11") (pintype "passive"))
    )
    (net (code "4") (name "/ANT_7_9") (class "Default")
      (node (ref "L303") (pin "1") (pinfunction "1_1") (pintype "passive"))
      (node (ref "R345") (pin "2") (pinfunction "2_2") (pintype "passive"))
      (node (ref "U301") (pin "8") (pinfunction "RF3_8") (pintype "passive"))
    )
    (net (code "5") (name "/ANT_10_12") (class "Default")
      (node (ref "L304") (pin "1") (pinfunction "1_1") (pintype "passive"))
      (node (ref "R347") (pin "2") (pinfunction "2_2") (pintype "passive"))
      (node (ref "U301") (pin "5") (pinfunction "RF4_5") (pintype "passive"))
    )
    (net (code "6") (name "/ANT_SEL_0") (class "Default")
      (node (ref "R349") (pin "1") (pinfunction "1_1") (pintype "passive"))
    )
    (net (code "7") (name "/ANT_SEL_1") (class "Default")
      (node (ref "R350") (pin "1") (pinfunction "1_1") (pintype "passive"))
    )
    (net (code "8") (name "/ANT_SEL_2") (class "Default")
      (node (ref "R351") (pin "1") (pinfunction "1_1") (pintype "passive"))
    )
    (net (code "9") (name "/ANT_SEL_3") (class "Default")
      (node (ref "R352") (pin "1") (pinfunction "1_1") (pintype "passive"))
    )
    (net (code "10") (name "3V3RF") (class "Default")
      (node (ref "C301") (pin "2") (pinfunction "2_2") (pintype "passive"))
      (node (ref "C302") (pin "2") (pinfunction "2_2") (pintype "passive"))
      (node (ref "C304") (pin "2") (pinfunction "2_2") (pintype "passive"))
      (node (ref "C305") (pin "2") (pinfunction "2_2") (pintype "passive"))
      (node (ref "C307") (pin "2") (pinfunction "2_2") (pintype "passive"))
      (node (ref "C308") (pin "2") (pinfunction "2_2") (pintype "passive"))
      (node (ref "C310") (pin "2") (pinfunction "2_2") (pintype "passive"))
      (node (ref "C311") (pin "2") (pinfunction "2_2") (pintype "passive"))
      (node (ref "C313") (pin "2") (pinfunction "2_2") (pintype "passive"))
      (node (ref "C314") (pin "2") (pinfunction "2_2") (pintype "passive"))
      (node (ref "C316") (pin "2") (pinfunction "2_2") (pintype "passive"))
      (node (ref "C318") (pin "2") (pinfunction "2_2") (pintype "passive"))
      (node (ref "C320") (pin "2") (pinfunction "2_2") (pintype "passive"))
      (node (ref "C322") (pin "2") (pinfunction "2_2") (pintype "passive"))
      (node (ref "C324") (pin "2") (pinfunction "2_2") (pintype "passive"))
      (node (ref "U301") (pin "16") (pinfunction "VDD_16") (pintype "power_in"))
      (node (ref "U302") (pin "16") (pinfunction "VDD_16") (pintype "power_in"))
      (node (ref "U303") (pin "16") (pinfunction "VDD_16") (pintype "power_in"))
      (node (ref "U304") (pin "16") (pinfunction "VDD_16") (pintype "power_in"))
      (node (ref "U305") (pin "16") (pinfunction "VDD_16") (pintype "power_in"))
    )
    (net (code "11") (name "3V3RFN") (class "Default")
      (node (ref "C303") (pin "2") (pinfunction "2_2") (pintype "passive"))
      (node (ref "C306") (pin "2") (pinfunction "2_2") (pintype "passive"))
      (node (ref "C309") (pin "2") (pinfunction "2_2") (pintype "passive"))
      (node (ref "C312") (pin "2") (pinfunction "2_2") (pintype "passive"))
      (node (ref "C315") (pin "2") (pinfunction "2_2") (pintype "passive"))
      (node (ref "C317") (pin "2") (pinfunction "2_2") (pintype "passive"))
      (node (ref "C319") (pin "2") (pinfunction "2_2") (pintype "passive"))
      (node (ref "C321") (pin "2") (pinfunction "2_2") (pintype "passive"))
      (node (ref "C323") (pin "2") (pinfunction "2_2") (pintype "passive"))
      (node (ref "C325") (pin "2") (pinfunction "2_2") (pintype "passive"))
      (node (ref "U301") (pin "20") (pinfunction "VSS_EXT_20") (pintype "power_in"))
      (node (ref "U302") (pin "20") (pinfunction "VSS_EXT_20") (pintype "power_in"))
      (node (ref "U303") (pin "20") (pinfunction "VSS_EXT_20") (pintype "power_in"))
      (node (ref "U304") (pin "20") (pinfunction "VSS_EXT_20") (pintype "power_in"))
      (node (ref "U305") (pin "20") (pinfunction "VSS_EXT_20") (pintype "power_in"))
    )
    (net (code "12") (name "GND") (class "Default")
      (node (ref "C301") (pin "1") (pinfunction "1_1") (pintype "passive"))
      (node (ref "C302") (pin "1") (pinfunction "1_1") (pintype "passive"))
      (node (ref "C303") (pin "1") (pinfunction "1_1") (pintype "passive"))
      (node (ref "C304") (pin "1") (pinfunction "1_1") (pintype "passive"))
      (node (ref "C305") (pin "1") (pinfunction "1_1") (pintype "passive"))
      (node (ref "C306") (pin "1") (pinfunction "1_1") (pintype "passive"))
      (node (ref "C307") (pin "1") (pinfunction "1_1") (pintype "passive"))
      (node (ref "C308") (pin "1") (pinfunction "1_1") (pintype "passive"))
      (node (ref "C309") (pin "1") (pinfunction "1_1") (pintype "passive"))
      (node (ref "C310") (pin "1") (pinfunction "1_1") (pintype "passive"))
      (node (ref "C311") (pin "1") (pinfunction "1_1") (pintype "passive"))
      (node (ref "C312") (pin "1") (pinfunction "1_1") (pintype "passive"))
      (node (ref "C313") (pin "1") (pinfunction "1_1") (pintype "passive"))
      (node (ref "C314") (pin "1") (pinfunction "1_1") (pintype "passive"))
      (node (ref "C315") (pin "1") (pinfunction "1_1") (pintype "passive"))
      (node (ref "C316") (pin "1") (pinfunction "1_1") (pintype "passive"))
      (node (ref "C317") (pin "1") (pinfunction "1_1") (pintype "passive"))
      (node (ref "C318") (pin "1") (pinfunction "1_1") (pintype "passive"))
      (node (ref "C319") (pin "1") (pinfunction "1_1") (pintype "passive"))
      (node (ref "C320") (pin "1") (pinfunction "1_1") (pintype "passive"))
      (node (ref "C321") (pin "1") (pinfunction "1_1") (pintype "passive"))
      (node (ref "C322") (pin "1") (pinfunction "1_1") (pintype "passive"))
      (node (ref "C323") (pin "1") (pinfunction "1_1") (pintype "passive"))
      (node (ref "C324") (pin "1") (pinfunction "1_1") (pintype "passive"))
      (node (ref "C325") (pin "1") (pinfunction "1_1") (pintype "passive"))
      (node (ref "C326") (pin "1") (pinfunction "1_1") (pintype "passive"))
      (node (ref "C327") (pin "1") (pinfunction "1_1") (pintype "passive"))
      (node (ref "C328") (pin "1") (pinfunction "1_1") (pintype "passive"))
      (node (ref "C329") (pin "1") (pinfunction "1_1") (pintype "passive"))
      (node (ref "L305") (pin "1") (pinfunction "1_1") (pintype "passive"))
      (node (ref "L306") (pin "1") (pinfunction "1_1") (pintype "passive"))
      (node (ref "L307") (pin "1") (pinfunction "1_1") (pintype "passive"))
      (node (ref "L308") (pin "1") (pinfunction "1_1") (pintype "passive"))
      (node (ref "L309") (pin "1") (pinfunction "1_1") (pintype "passive"))
      (node (ref "L310") (pin "1") (pinfunction "1_1") (pintype "passive"))
      (node (ref "L311") (pin "1") (pinfunction "1_1") (pintype "passive"))
      (node (ref "L312") (pin "1") (pinfunction "1_1") (pintype "passive"))
      (node (ref "L313") (pin "1") (pinfunction "1_1") (pintype "passive"))
      (node (ref "L314") (pin "1") (pinfunction "1_1") (pintype "passive"))
      (node (ref "L315") (pin "1") (pinfunction "1_1") (pintype "passive"))
      (node (ref "L316") (pin "1") (pinfunction "1_1") (pintype "passive"))
      (node (ref "R302") (pin "1") (pinfunction "1_1") (pintype "passive"))
      (node (ref "R305") (pin "1") (pinfunction "1_1") (pintype "passive"))
      (node (ref "R308") (pin "1") (pinfunction "1_1") (pintype "passive"))
      (node (ref "R311") (pin "1") (pinfunction "1_1") (pintype "passive"))
      (node (ref "R314") (pin "1") (pinfunction "1_1") (pintype "passive"))
      (node (ref "R317") (pin "1") (pinfunction "1_1") (pintype "passive"))
      (node (ref "R320") (pin "1") (pinfunction "1_1") (pintype "passive"))
      (node (ref "R323") (pin "1") (pinfunction "1_1") (pintype "passive"))
      (node (ref "R326") (pin "1") (pinfunction "1_1") (pintype "passive"))
      (node (ref "R329") (pin "1") (pinfunction "1_1") (pintype "passive"))
      (node (ref "R332") (pin "1") (pinfunction "1_1") (pintype "passive"))
      (node (ref "R335") (pin "1") (pinfunction "1_1") (pintype "passive"))
      (node (ref "R337") (pin "2") (pinfunction "2_2") (pintype "passive"))
      (node (ref "R338") (pin "2") (pinfunction "2_2") (pintype "passive"))
      (node (ref "R339") (pin "2") (pinfunction "2_2") (pintype "passive"))
      (node (ref "R340") (pin "2") (pinfunction "2_2") (pintype "passive"))
      (node (ref "R341") (pin "1") (pinfunction "1_1") (pintype "passive"))
      (node (ref "R342") (pin "1") (pinfunction "1_1") (pintype "passive"))
      (node (ref "R343") (pin "1") (pinfunction "1_1") (pintype "passive"))
      (node (ref "R344") (pin "1") (pinfunction "1_1") (pintype "passive"))
      (node (ref "R345") (pin "1") (pinfunction "1_1") (pintype "passive"))
      (node (ref "R346") (pin "1") (pinfunction "1_1") (pintype "passive"))
      (node (ref "R347") (pin "1") (pinfunction "1_1") (pintype "passive"))
      (node (ref "R348") (pin "1") (pinfunction "1_1") (pintype "passive"))
      (node (ref "U301") (pin "1") (pinfunction "GND1_1") (pintype "power_in"))
      (node (ref "U301") (pin "10") (pinfunction "GND8_10") (pintype "power_in"))
      (node (ref "U301") (pin "12") (pinfunction "GND9_12") (pintype "power_in"))
      (node (ref "U301") (pin "13") (pinfunction "GND10_13") (pintype "power_in"))
      (node (ref "U301") (pin "15") (pinfunction "GND11_15") (pintype "power_in"))
      (node (ref "U301") (pin "19") (pinfunction "V3_19") (pintype "passive"))
      (node (ref "U301") (pin "2") (pinfunction "GND2_2") (pintype "power_in"))
      (node (ref "U301") (pin "21") (pinfunction "GND12_21") (pintype "power_in"))
      (node (ref "U301") (pin "23") (pinfunction "GND14_23") (pintype "power_in"))
      (node (ref "U301") (pin "24") (pinfunction "GND13_24") (pintype "power_in"))
      (node (ref "U301") (pin "25") (pinfunction "EXP_PAD_25") (pintype "power_in"))
      (node (ref "U301") (pin "3") (pinfunction "GND3_3") (pintype "power_in"))
      (node (ref "U301") (pin "4") (pinfunction "GND4_4") (pintype "power_in"))
      (node (ref "U301") (pin "6") (pinfunction "GND5_6") (pintype "power_in"))
      (node (ref "U301") (pin "7") (pinfunction "GND6_7") (pintype "power_in"))
      (node (ref "U301") (pin "9") (pinfunction "GND7_9") (pintype "power_in"))
      (node (ref "U302") (pin "1") (pinfunction "GND1_1") (pintype "power_in"))
      (node (ref "U302") (pin "10") (pinfunction "GND8_10") (pintype "power_in"))
      (node (ref "U302") (pin "12") (pinfunction "GND9_12") (pintype "power_in"))
      (node (ref "U302") (pin "13") (pinfunction "GND10_13") (pintype "power_in"))
      (node (ref "U302") (pin "15") (pinfunction "GND11_15") (pintype "power_in"))
      (node (ref "U302") (pin "19") (pinfunction "V3_19") (pintype "passive"))
      (node (ref "U302") (pin "2") (pinfunction "GND2_2") (pintype "power_in"))
      (node (ref "U302") (pin "21") (pinfunction "GND12_21") (pintype "power_in"))
      (node (ref "U302") (pin "23") (pinfunction "GND14_23") (pintype "power_in"))
      (node (ref "U302") (pin "24") (pinfunction "GND13_24") (pintype "power_in"))
      (node (ref "U302") (pin "25") (pinfunction "EXP_PAD_25") (pintype "power_in"))
      (node (ref "U302") (pin "3") (pinfunction "GND3_3") (pintype "power_in"))
      (node (ref "U302") (pin "4") (pinfunction "GND4_4") (pintype "power_in"))
      (node (ref "U302") (pin "6") (pinfunction "GND5_6") (pintype "power_in"))
      (node (ref "U302") (pin "7") (pinfunction "GND6_7") (pintype "power_in"))
      (node (ref "U302") (pin "9") (pinfunction "GND7_9") (pintype "power_in"))
      (node (ref "U303") (pin "1") (pinfunction "GND1_1") (pintype "power_in"))
      (node (ref "U303") (pin "10") (pinfunction "GND8_10") (pintype "power_in"))
      (node (ref "U303") (pin "12") (pinfunction "GND9_12") (pintype "power_in"))
      (node (ref "U303") (pin "13") (pinfunction "GND10_13") (pintype "power_in"))
      (node (ref "U303") (pin "15") (pinfunction "GND11_15") (pintype "power_in"))
      (node (ref "U303") (pin "19") (pinfunction "V3_19") (pintype "passive"))
      (node (ref "U303") (pin "2") (pinfunction "GND2_2") (pintype "power_in"))
      (node (ref "U303") (pin "21") (pinfunction "GND12_21") (pintype "power_in"))
      (node (ref "U303") (pin "23") (pinfunction "GND14_23") (pintype "power_in"))
      (node (ref "U303") (pin "24") (pinfunction "GND13_24") (pintype "power_in"))
      (node (ref "U303") (pin "25") (pinfunction "EXP_PAD_25") (pintype "power_in"))
      (node (ref "U303") (pin "3") (pinfunction "GND3_3") (pintype "power_in"))
      (node (ref "U303") (pin "4") (pinfunction "GND4_4") (pintype "power_in"))
      (node (ref "U303") (pin "6") (pinfunction "GND5_6") (pintype "power_in"))
      (node (ref "U303") (pin "7") (pinfunction "GND6_7") (pintype "power_in"))
      (node (ref "U303") (pin "9") (pinfunction "GND7_9") (pintype "power_in"))
      (node (ref "U304") (pin "1") (pinfunction "GND1_1") (pintype "power_in"))
      (node (ref "U304") (pin "10") (pinfunction "GND8_10") (pintype "power_in"))
      (node (ref "U304") (pin "12") (pinfunction "GND9_12") (pintype "power_in"))
      (node (ref "U304") (pin "13") (pinfunction "GND10_13") (pintype "power_in"))
      (node (ref "U304") (pin "15") (pinfunction "GND11_15") (pintype "power_in"))
      (node (ref "U304") (pin "19") (pinfunction "V3_19") (pintype "passive"))
      (node (ref "U304") (pin "2") (pinfunction "GND2_2") (pintype "power_in"))
      (node (ref "U304") (pin "21") (pinfunction "GND12_21") (pintype "power_in"))
      (node (ref "U304") (pin "23") (pinfunction "GND14_23") (pintype "power_in"))
      (node (ref "U304") (pin "24") (pinfunction "GND13_24") (pintype "power_in"))
      (node (ref "U304") (pin "25") (pinfunction "EXP_PAD_25") (pintype "power_in"))
      (node (ref "U304") (pin "3") (pinfunction "GND3_3") (pintype "power_in"))
      (node (ref "U304") (pin "4") (pinfunction "GND4_4") (pintype "power_in"))
      (node (ref "U304") (pin "6") (pinfunction "GND5_6") (pintype "power_in"))
      (node (ref "U304") (pin "7") (pinfunction "GND6_7") (pintype "power_in"))
      (node (ref "U304") (pin "9") (pinfunction "GND7_9") (pintype "power_in"))
      (node (ref "U305") (pin "1") (pinfunction "GND1_1") (pintype "power_in"))
      (node (ref "U305") (pin "10") (pinfunction "GND8_10") (pintype "power_in"))
      (node (ref "U305") (pin "12") (pinfunction "GND9_12") (pintype "power_in"))
      (node (ref "U305") (pin "13") (pinfunction "GND10_13") (pintype "power_in"))
      (node (ref "U305") (pin "15") (pinfunction "GND11_15") (pintype "power_in"))
      (node (ref "U305") (pin "19") (pinfunction "V3_19") (pintype "passive"))
      (node (ref "U305") (pin "2") (pinfunction "GND2_2") (pintype "power_in"))
      (node (ref "U305") (pin "21") (pinfunction "GND12_21") (pintype "power_in"))
      (node (ref "U305") (pin "23") (pinfunction "GND14_23") (pintype "power_in"))
      (node (ref "U305") (pin "24") (pinfunction "GND13_24") (pintype "power_in"))
      (node (ref "U305") (pin "25") (pinfunction "EXP_PAD_25") (pintype "power_in"))
      (node (ref "U305") (pin "3") (pinfunction "GND3_3") (pintype "power_in"))
      (node (ref "U305") (pin "4") (pinfunction "GND4_4") (pintype "power_in"))
      (node (ref "U305") (pin "6") (pinfunction "GND5_6") (pintype "power_in"))
      (node (ref "U305") (pin "7") (pinfunction "GND6_7") (pintype "power_in"))
      (node (ref "U305") (pin "9") (pinfunction "GND7_9") (pintype "power_in"))
      (node (ref "V301") (pin "2") (pintype "passive"))
      (node (ref "V302") (pin "2") (pintype "passive"))
      (node (ref "V303") (pin "2") (pintype "passive"))
      (node (ref "V304") (pin "2") (pintype "passive"))
      (node (ref "V305") (pin "2") (pintype "passive"))
      (node (ref "V306") (pin "2") (pintype "passive"))
      (node (ref "V307") (pin "2") (pintype "passive"))
      (node (ref "V308") (pin "2") (pintype "passive"))
      (node (ref "V309") (pin "2") (pintype "passive"))
      (node (ref "V310") (pin "2") (pintype "passive"))
      (node (ref "V311") (pin "2") (pintype "passive"))
      (node (ref "V312") (pin "2") (pintype "passive"))
    )
    (net (code "13") (name "Net-(ANT_1-Pad1)") (class "Default")
      (node (ref "ANT_1") (pin "1") (pinfunction "1_1") (pintype "passive"))
      (node (ref "C330") (pin "2") (pinfunction "2_2") (pintype "passive"))
      (node (ref "V301") (pin "1") (pintype "passive"))
    )
    (net (code "14") (name "Net-(ANT_2-Pad1)") (class "Default")
      (node (ref "ANT_2") (pin "1") (pinfunction "1_1") (pintype "passive"))
      (node (ref "C331") (pin "2") (pinfunction "2_2") (pintype "passive"))
      (node (ref "V302") (pin "1") (pintype "passive"))
    )
    (net (code "15") (name "Net-(ANT_3-Pad1)") (class "Default")
      (node (ref "ANT_3") (pin "1") (pinfunction "1_1") (pintype "passive"))
      (node (ref "C332") (pin "2") (pinfunction "2_2") (pintype "passive"))
      (node (ref "V303") (pin "1") (pintype "passive"))
    )
    (net (code "16") (name "Net-(ANT_4-Pad1)") (class "Default")
      (node (ref "ANT_4") (pin "1") (pinfunction "1_1") (pintype "passive"))
      (node (ref "C333") (pin "2") (pinfunction "2_2") (pintype "passive"))
      (node (ref "V304") (pin "1") (pintype "passive"))
    )
    (net (code "17") (name "Net-(ANT_5-Pad1)") (class "Default")
      (node (ref "ANT_5") (pin "1") (pinfunction "1_1") (pintype "passive"))
      (node (ref "C334") (pin "2") (pinfunction "2_2") (pintype "passive"))
      (node (ref "V305") (pin "1") (pintype "passive"))
    )
    (net (code "18") (name "Net-(ANT_6-Pad1)") (class "Default")
      (node (ref "ANT_6") (pin "1") (pinfunction "1_1") (pintype "passive"))
      (node (ref "C335") (pin "2") (pinfunction "2_2") (pintype "passive"))
      (node (ref "V306") (pin "1") (pintype "passive"))
    )
    (net (code "19") (name "Net-(ANT_7-Pad1)") (class "Default")
      (node (ref "ANT_7") (pin "1") (pinfunction "1_1") (pintype "passive"))
      (node (ref "C336") (pin "2") (pinfunction "2_2") (pintype "passive"))
      (node (ref "V307") (pin "1") (pintype "passive"))
    )
    (net (code "20") (name "Net-(ANT_8-Pad1)") (class "Default")
      (node (ref "ANT_8") (pin "1") (pinfunction "1_1") (pintype "passive"))
      (node (ref "C337") (pin "2") (pinfunction "2_2") (pintype "passive"))
      (node (ref "V308") (pin "1") (pintype "passive"))
    )
    (net (code "21") (name "Net-(ANT_9-Pad1)") (class "Default")
      (node (ref "ANT_9") (pin "1") (pinfunction "1_1") (pintype "passive"))
      (node (ref "C338") (pin "2") (pinfunction "2_2") (pintype "passive"))
      (node (ref "V309") (pin "1") (pintype "passive"))
    )
    (net (code "22") (name "Net-(ANT_10-Pad1)") (class "Default")
      (node (ref "ANT_10") (pin "1") (pinfunction "1_1") (pintype "passive"))
      (node (ref "C339") (pin "2") (pinfunction "2_2") (pintype "passive"))
      (node (ref "V310") (pin "1") (pintype "passive"))
    )
    (net (code "23") (name "Net-(ANT_11-Pad1)") (class "Default")
      (node (ref "ANT_11") (pin "1") (pinfunction "1_1") (pintype "passive"))
      (node (ref "C340") (pin "2") (pinfunction "2_2") (pintype "passive"))
      (node (ref "V311") (pin "1") (pintype "passive"))
    )
    (net (code "24") (name "Net-(ANT_12-Pad1)") (class "Default")
      (node (ref "ANT_12") (pin "1") (pinfunction "1_1") (pintype "passive"))
      (node (ref "C341") (pin "2") (pinfunction "2_2") (pintype "passive"))
      (node (ref "V312") (pin "1") (pintype "passive"))
    )
    (net (code "25") (name "Net-(C330-Pad1)") (class "Default")
      (node (ref "C330") (pin "1") (pinfunction "1_1") (pintype "passive"))
      (node (ref "L305") (pin "2") (pinfunction "2_2") (pintype "passive"))
      (node (ref "R301") (pin "2") (pinfunction "2_2") (pintype "passive"))
    )
    (net (code "26") (name "Net-(C331-Pad1)") (class "Default")
      (node (ref "C331") (pin "1") (pinfunction "1_1") (pintype "passive"))
      (node (ref "L306") (pin "2") (pinfunction "2_2") (pintype "passive"))
      (node (ref "R304") (pin "2") (pinfunction "2_2") (pintype "passive"))
    )
    (net (code "27") (name "Net-(C332-Pad1)") (class "Default")
      (node (ref "C332") (pin "1") (pinfunction "1_1") (pintype "passive"))
      (node (ref "L307") (pin "2") (pinfunction "2_2") (pintype "passive"))
      (node (ref "R307") (pin "2") (pinfunction "2_2") (pintype "passive"))
    )
    (net (code "28") (name "Net-(C333-Pad1)") (class "Default")
      (node (ref "C333") (pin "1") (pinfunction "1_1") (pintype "passive"))
      (node (ref "L308") (pin "2") (pinfunction "2_2") (pintype "passive"))
      (node (ref "R310") (pin "2") (pinfunction "2_2") (pintype "passive"))
    )
    (net (code "29") (name "Net-(C334-Pad1)") (class "Default")
      (node (ref "C334") (pin "1") (pinfunction "1_1") (pintype "passive"))
      (node (ref "L309") (pin "2") (pinfunction "2_2") (pintype "passive"))
      (node (ref "R313") (pin "2") (pinfunction "2_2") (pintype "passive"))
    )
    (net (code "30") (name "Net-(C335-Pad1)") (class "Default")
      (node (ref "C335") (pin "1") (pinfunction "1_1") (pintype "passive"))
      (node (ref "L310") (pin "2") (pinfunction "2_2") (pintype "passive"))
      (node (ref "R316") (pin "2") (pinfunction "2_2") (pintype "passive"))
    )
    (net (code "31") (name "Net-(C336-Pad1)") (class "Default")
      (node (ref "C336") (pin "1") (pinfunction "1_1") (pintype "passive"))
      (node (ref "L311") (pin "2") (pinfunction "2_2") (pintype "passive"))
      (node (ref "R319") (pin "2") (pinfunction "2_2") (pintype "passive"))
    )
    (net (code "32") (name "Net-(C337-Pad1)") (class "Default")
      (node (ref "C337") (pin "1") (pinfunction "1_1") (pintype "passive"))
      (node (ref "L312") (pin "2") (pinfunction "2_2") (pintype "passive"))
      (node (ref "R322") (pin "2") (pinfunction "2_2") (pintype "passive"))
    )
    (net (code "33") (name "Net-(C338-Pad1)") (class "Default")
      (node (ref "C338") (pin "1") (pinfunction "1_1") (pintype "passive"))
      (node (ref "L313") (pin "2") (pinfunction "2_2") (pintype "passive"))
      (node (ref "R325") (pin "2") (pinfunction "2_2") (pintype "passive"))
    )
    (net (code "34") (name "Net-(C339-Pad1)") (class "Default")
      (node (ref "C339") (pin "1") (pinfunction "1_1") (pintype "passive"))
      (node (ref "L314") (pin "2") (pinfunction "2_2") (pintype "passive"))
      (node (ref "R328") (pin "2") (pinfunction "2_2") (pintype "passive"))
    )
    (net (code "35") (name "Net-(C340-Pad1)") (class "Default")
      (node (ref "C340") (pin "1") (pinfunction "1_1") (pintype "passive"))
      (node (ref "L315") (pin "2") (pinfunction "2_2") (pintype "passive"))
      (node (ref "R331") (pin "2") (pinfunction "2_2") (pintype "passive"))
    )
    (net (code "36") (name "Net-(C341-Pad1)") (class "Default")
      (node (ref "C341") (pin "1") (pinfunction "1_1") (pintype "passive"))
      (node (ref "L316") (pin "2") (pinfunction "2_2") (pintype "passive"))
      (node (ref "R334") (pin "2") (pinfunction "2_2") (pintype "passive"))
    )
    (net (code "37") (name "Net-(U301-V1)") (class "Default")
      (node (ref "C327") (pin "2") (pinfunction "2_2") (pintype "passive"))
      (node (ref "R351") (pin "2") (pinfunction "2_2") (pintype "passive"))
      (node (ref "TP303") (pin "1") (pinfunction "1_1") (pintype "passive"))
      (node (ref "U301") (pin "17") (pinfunction "V1_17") (pintype "passive"))
    )
    (net (code "38") (name "Net-(U301-V2)") (class "Default")
      (node (ref "C326") (pin "2") (pinfunction "2_2") (pintype "passive"))
      (node (ref "R352") (pin "2") (pinfunction "2_2") (pintype "passive"))
      (node (ref "TP304") (pin "1") (pinfunction "1_1") (pintype "passive"))
      (node (ref "U301") (pin "18") (pinfunction "V2_18") (pintype "passive"))
    )
    (net (code "39") (name "Net-(U302-RF1)") (class "Default")
      (node (ref "R301") (pin "1") (pinfunction "1_1") (pintype "passive"))
      (node (ref "R302") (pin "2") (pinfunction "2_2") (pintype "passive"))
      (node (ref "U302") (pin "14") (pinfunction "RF1_14") (pintype "passive"))
    )
    (net (code "40") (name "Net-(U302-RF2)") (class "Default")
      (node (ref "R304") (pin "1") (pinfunction "1_1") (pintype "passive"))
      (node (ref "R305") (pin "2") (pinfunction "2_2") (pintype "passive"))
      (node (ref "U302") (pin "11") (pinfunction "RF2_11") (pintype "passive"))
    )
    (net (code "41") (name "Net-(U302-RF3)") (class "Default")
      (node (ref "R337") (pin "1") (pinfunction "1_1") (pintype "passive"))
      (node (ref "U302") (pin "8") (pinfunction "RF3_8") (pintype "passive"))
    )
    (net (code "42") (name "Net-(U302-RF4)") (class "Default")
      (node (ref "R307") (pin "1") (pinfunction "1_1") (pintype "passive"))
      (node (ref "R308") (pin "2") (pinfunction "2_2") (pintype "passive"))
      (node (ref "U302") (pin "5") (pinfunction "RF4_5") (pintype "passive"))
    )
    (net (code "43") (name "Net-(U302-RFC)") (class "Default")
      (node (ref "L301") (pin "2") (pinfunction "2_2") (pintype "passive"))
      (node (ref "R342") (pin "2") (pinfunction "2_2") (pintype "passive"))
      (node (ref "U302") (pin "22") (pinfunction "RFC_22") (pintype "passive"))
    )
    (net (code "44") (name "Net-(U302-V1)") (class "Default")
      (node (ref "C329") (pin "2") (pinfunction "2_2") (pintype "passive"))
      (node (ref "R349") (pin "2") (pinfunction "2_2") (pintype "passive"))
      (node (ref "TP301") (pin "1") (pinfunction "1_1") (pintype "passive"))
      (node (ref "U302") (pin "17") (pinfunction "V1_17") (pintype "passive"))
      (node (ref "U303") (pin "17") (pinfunction "V1_17") (pintype "passive"))
      (node (ref "U304") (pin "17") (pinfunction "V1_17") (pintype "passive"))
      (node (ref "U305") (pin "17") (pinfunction "V1_17") (pintype "passive"))
    )
    (net (code "45") (name "Net-(U302-V2)") (class "Default")
      (node (ref "C328") (pin "2") (pinfunction "2_2") (pintype "passive"))
      (node (ref "R350") (pin "2") (pinfunction "2_2") (pintype "passive"))
      (node (ref "TP302") (pin "1") (pinfunction "1_1") (pintype "passive"))
      (node (ref "U302") (pin "18") (pinfunction "V2_18") (pintype "passive"))
      (node (ref "U303") (pin "18") (pinfunction "V2_18") (pintype "passive"))
      (node (ref "U304") (pin "18") (pinfunction "V2_18") (pintype "passive"))
      (node (ref "U305") (pin "18") (pinfunction "V2_18") (pintype "passive"))
    )
    (net (code "46") (name "Net-(U303-RF1)") (class "Default")
      (node (ref "R310") (pin "1") (pinfunction "1_1") (pintype "passive"))
      (node (ref "R311") (pin "2") (pinfunction "2_2") (pintype "passive"))
      (node (ref "U303") (pin "14") (pinfunction "RF1_14") (pintype "passive"))
    )
    (net (code "47") (name "Net-(U303-RF2)") (class "Default")
      (node (ref "R313") (pin "1") (pinfunction "1_1") (pintype "passive"))
      (node (ref "R314") (pin "2") (pinfunction "2_2") (pintype "passive"))
      (node (ref "U303") (pin "11") (pinfunction "RF2_11") (pintype "passive"))
    )
    (net (code "48") (name "Net-(U303-RF3)") (class "Default")
      (node (ref "R338") (pin "1") (pinfunction "1_1") (pintype "passive"))
      (node (ref "U303") (pin "8") (pinfunction "RF3_8") (pintype "passive"))
    )
    (net (code "49") (name "Net-(U303-RF4)") (class "Default")
      (node (ref "R316") (pin "1") (pinfunction "1_1") (pintype "passive"))
      (node (ref "R317") (pin "2") (pinfunction "2_2") (pintype "passive"))
      (node (ref "U303") (pin "5") (pinfunction "RF4_5") (pintype "passive"))
    )
    (net (code "50") (name "Net-(U303-RFC)") (class "Default")
      (node (ref "L302") (pin "2") (pinfunction "2_2") (pintype "passive"))
      (node (ref "R344") (pin "2") (pinfunction "2_2") (pintype "passive"))
      (node (ref "U303") (pin "22") (pinfunction "RFC_22") (pintype "passive"))
    )
    (net (code "51") (name "Net-(U304-RF1)") (class "Default")
      (node (ref "R319") (pin "1") (pinfunction "1_1") (pintype "passive"))
      (node (ref "R320") (pin "2") (pinfunction "2_2") (pintype "passive"))
      (node (ref "U304") (pin "14") (pinfunction "RF1_14") (pintype "passive"))
    )
    (net (code "52") (name "Net-(U304-RF2)") (class "Default")
      (node (ref "R322") (pin "1") (pinfunction "1_1") (pintype "passive"))
      (node (ref "R323") (pin "2") (pinfunction "2_2") (pintype "passive"))
      (node (ref "U304") (pin "11") (pinfunction "RF2_11") (pintype "passive"))
    )
    (net (code "53") (name "Net-(U304-RF3)") (class "Default")
      (node (ref "R339") (pin "1") (pinfunction "1_1") (pintype "passive"))
      (node (ref "U304") (pin "8") (pinfunction "RF3_8") (pintype "passive"))
    )
    (net (code "54") (name "Net-(U304-RF4)") (class "Default")
      (node (ref "R325") (pin "1") (pinfunction "1_1") (pintype "passive"))
      (node (ref "R326") (pin "2") (pinfunction "2_2") (pintype "passive"))
      (node (ref "U304") (pin "5") (pinfunction "RF4_5") (pintype "passive"))
    )
    (net (code "55") (name "Net-(U304-RFC)") (class "Default")
      (node (ref "L303") (pin "2") (pinfunction "2_2") (pintype "passive"))
      (node (ref "R346") (pin "2") (pinfunction "2_2") (pintype "passive"))
      (node (ref "U304") (pin "22") (pinfunction "RFC_22") (pintype "passive"))
    )
    (net (code "56") (name "Net-(U305-RF1)") (class "Default")
      (node (ref "R328") (pin "1") (pinfunction "1_1") (pintype "passive"))
      (node (ref "R329") (pin "2") (pinfunction "2_2") (pintype "passive"))
      (node (ref "U305") (pin "14") (pinfunction "RF1_14") (pintype "passive"))
    )
    (net (code "57") (name "Net-(U305-RF2)") (class "Default")
      (node (ref "R331") (pin "1") (pinfunction "1_1") (pintype "passive"))
      (node (ref "R332") (pin "2") (pinfunction "2_2") (pintype "passive"))
      (node (ref "U305") (pin "11") (pinfunction "RF2_11") (pintype "passive"))
    )
    (net (code "58") (name "Net-(U305-RF3)") (class "Default")
      (node (ref "R340") (pin "1") (pinfunction "1_1") (pintype "passive"))
      (node (ref "U305") (pin "8") (pinfunction "RF3_8") (pintype "passive"))
    )
    (net (code "59") (name "Net-(U305-RF4)") (class "Default")
      (node (ref "R334") (pin "1") (pinfunction "1_1") (pintype "passive"))
      (node (ref "R335") (pin "2") (pinfunction "2_2") (pintype "passive"))
      (node (ref "U305") (pin "5") (pinfunction "RF4_5") (pintype "passive"))
    )
    (net (code "60") (name "Net-(U305-RFC)") (class "Default")
      (node (ref "L304") (pin "2") (pinfunction "2_2") (pintype "passive"))
      (node (ref "R348") (pin "2") (pinfunction "2_2") (pintype "passive"))
      (node (ref "U305") (pin "22") (pinfunction "RFC_22") (pintype "passive"))
    )
  )
)
